# FlasherPanel.net
KiCad netlist of a schematic drawn in EasyEDA Pro
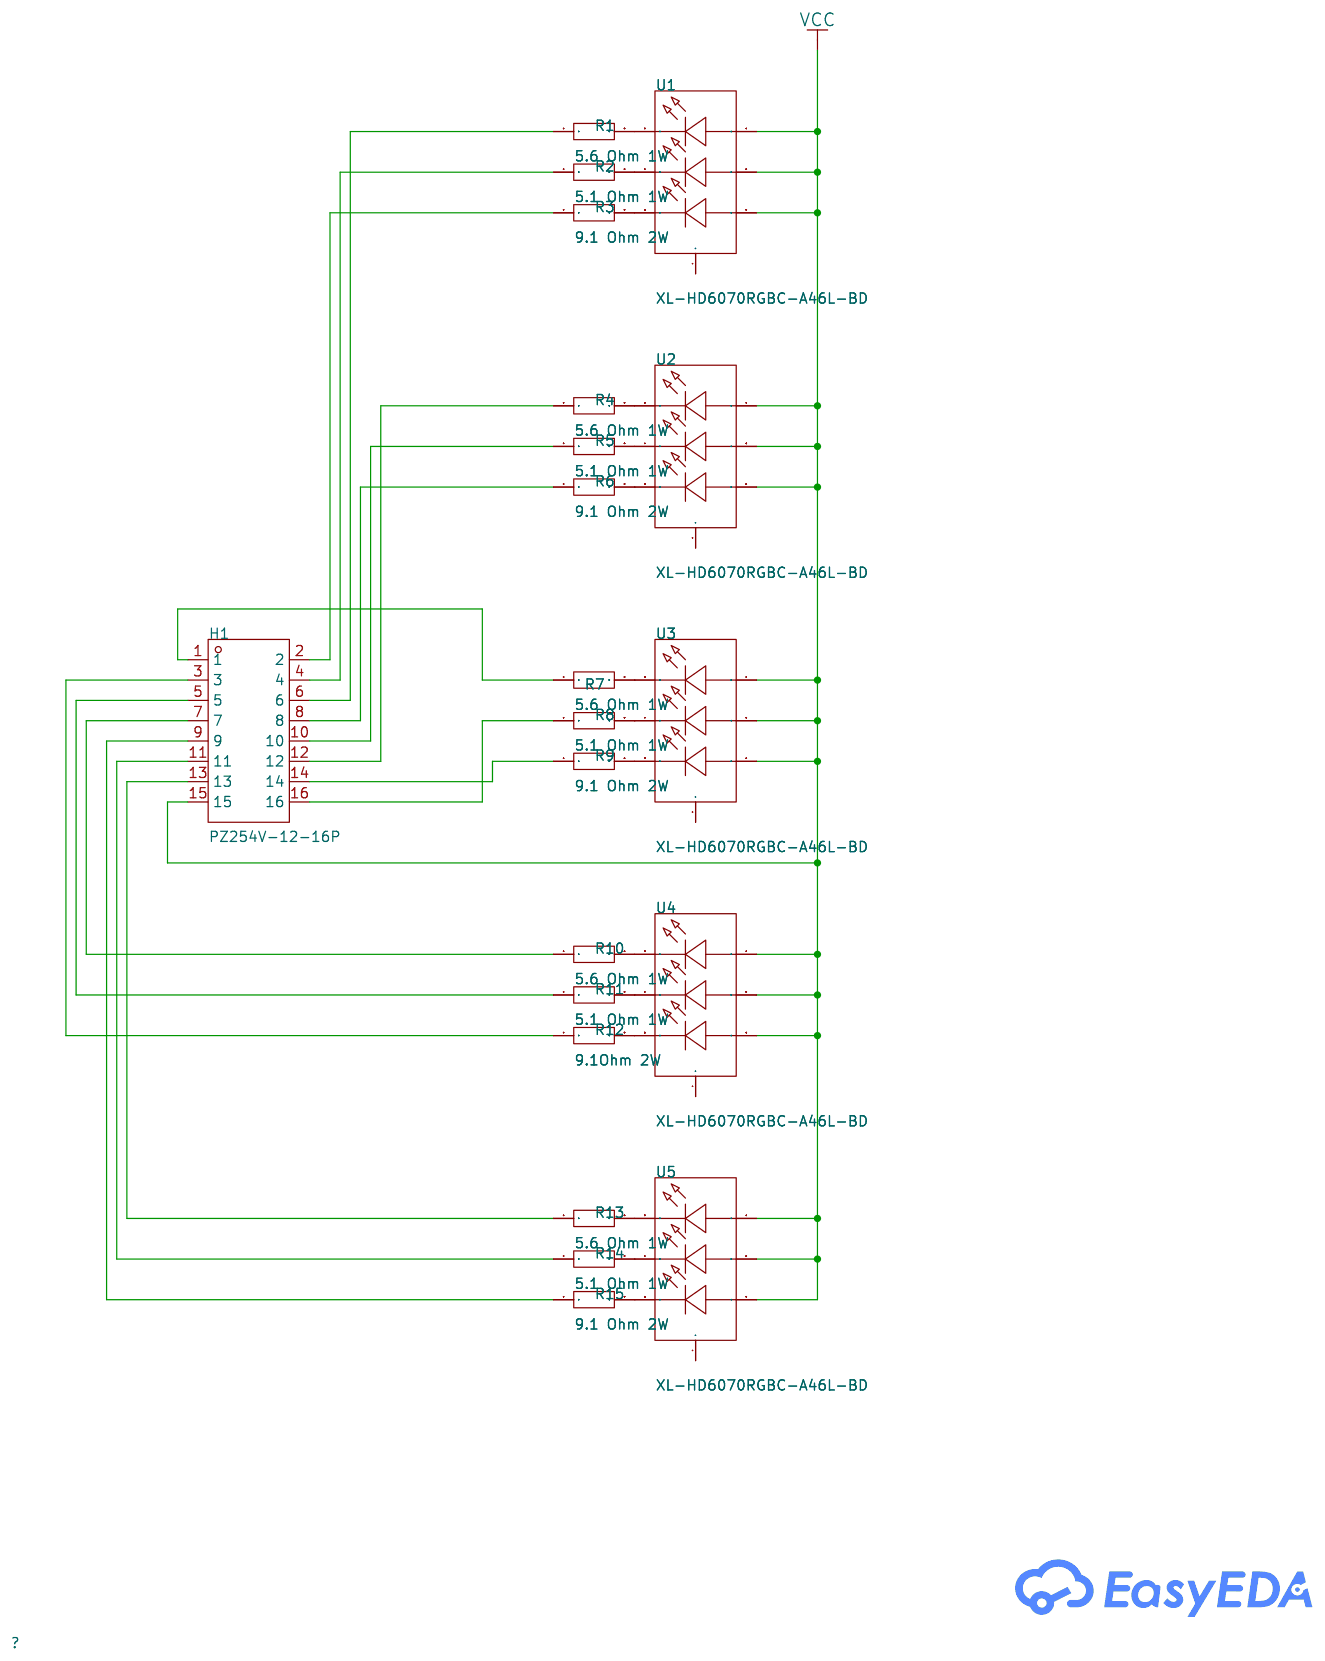
[diagram p0: schematic sheet]

(export (version "E")
  (design (tool "Eeschema 10.0.6"))
  (components
    (comp (ref "H1")
      (value "PZ254V-12-16P")
      (footprint "easyedapro:HDR-TH_16P-P2.54-V-M-R2-C8-S2.54")
      (fields (field (name "Manufacturer") "XFCN(兴飞)"))
      (libsource (lib "easyedapro") (part "PZ254V-12-16P"))
    )
    (comp (ref "R1")
      (value "5.6 Ohm 1W")
      (footprint "easyedapro:R0603")
      (libsource (lib "easyedapro") (part "Res"))
    )
    (comp (ref "R2")
      (value "5.1 Ohm 1W")
      (footprint "easyedapro:R0603")
      (libsource (lib "easyedapro") (part "Res"))
    )
    (comp (ref "R3")
      (value "9.1 Ohm 2W")
      (footprint "easyedapro:R0603")
      (libsource (lib "easyedapro") (part "Res"))
    )
    (comp (ref "R4")
      (value "5.6 Ohm 1W")
      (footprint "easyedapro:R0603")
      (libsource (lib "easyedapro") (part "Res"))
    )
    (comp (ref "R5")
      (value "5.1 Ohm 1W")
      (footprint "easyedapro:R0603")
      (libsource (lib "easyedapro") (part "Res"))
    )
    (comp (ref "R6")
      (value "9.1 Ohm 2W")
      (footprint "easyedapro:R0603")
      (libsource (lib "easyedapro") (part "Res"))
    )
    (comp (ref "R7")
      (value "5.6 Ohm 1W")
      (footprint "easyedapro:R0603")
      (libsource (lib "easyedapro") (part "Res"))
    )
    (comp (ref "R8")
      (value "5.1 Ohm 1W")
      (footprint "easyedapro:R0603")
      (libsource (lib "easyedapro") (part "Res"))
    )
    (comp (ref "R9")
      (value "9.1 Ohm 2W")
      (footprint "easyedapro:R0603")
      (libsource (lib "easyedapro") (part "Res"))
    )
    (comp (ref "R10")
      (value "5.6 Ohm 1W")
      (footprint "easyedapro:R0603")
      (libsource (lib "easyedapro") (part "Res"))
    )
    (comp (ref "R11")
      (value "5.1 Ohm 1W")
      (footprint "easyedapro:R0603")
      (libsource (lib "easyedapro") (part "Res"))
    )
    (comp (ref "R12")
      (value "9.1Ohm 2W")
      (footprint "easyedapro:R0603")
      (libsource (lib "easyedapro") (part "Res"))
    )
    (comp (ref "R13")
      (value "5.6 Ohm 1W")
      (footprint "easyedapro:R0603")
      (libsource (lib "easyedapro") (part "Res"))
    )
    (comp (ref "R14")
      (value "5.1 Ohm 1W")
      (footprint "easyedapro:R0603")
      (libsource (lib "easyedapro") (part "Res"))
    )
    (comp (ref "R15")
      (value "9.1 Ohm 2W")
      (footprint "easyedapro:R0603")
      (libsource (lib "easyedapro") (part "Res"))
    )
    (comp (ref "U1")
      (value "XL-HD6070RGBC-A46L-BD")
      (footprint "easyedapro:LED-SMD_6P-BD8.0-LS14.5")
      (fields (field (name "Manufacturer") "XINGLIGHT(成兴光)"))
      (libsource (lib "easyedapro") (part "XL-HD6070RGBC-A46L-BD"))
    )
    (comp (ref "U2")
      (value "XL-HD6070RGBC-A46L-BD")
      (footprint "easyedapro:LED-SMD_6P-BD8.0-LS14.5")
      (fields (field (name "Manufacturer") "XINGLIGHT(成兴光)"))
      (libsource (lib "easyedapro") (part "XL-HD6070RGBC-A46L-BD"))
    )
    (comp (ref "U3")
      (value "XL-HD6070RGBC-A46L-BD")
      (footprint "easyedapro:LED-SMD_6P-BD8.0-LS14.5")
      (fields (field (name "Manufacturer") "XINGLIGHT(成兴光)"))
      (libsource (lib "easyedapro") (part "XL-HD6070RGBC-A46L-BD"))
    )
    (comp (ref "U4")
      (value "XL-HD6070RGBC-A46L-BD")
      (footprint "easyedapro:LED-SMD_6P-BD8.0-LS14.5")
      (fields (field (name "Manufacturer") "XINGLIGHT(成兴光)"))
      (libsource (lib "easyedapro") (part "XL-HD6070RGBC-A46L-BD"))
    )
    (comp (ref "U5")
      (value "XL-HD6070RGBC-A46L-BD")
      (footprint "easyedapro:LED-SMD_6P-BD8.0-LS14.5")
      (fields (field (name "Manufacturer") "XINGLIGHT(成兴光)"))
      (libsource (lib "easyedapro") (part "XL-HD6070RGBC-A46L-BD"))
    )
  )
  (nets
    (net (code "1") (name "Net-(H1-Pad1)") (class "Default")
      (node (ref "H1") (pin "1") (pinfunction "1_1") (pintype "unspecified"))
      (node (ref "R7") (pin "1") (pinfunction "1_1") (pintype "input"))
    )
    (net (code "2") (name "Net-(H1-Pad2)") (class "Default")
      (node (ref "H1") (pin "2") (pinfunction "2_2") (pintype "unspecified"))
      (node (ref "R3") (pin "1") (pinfunction "1_1") (pintype "input"))
    )
    (net (code "3") (name "Net-(H1-Pad3)") (class "Default")
      (node (ref "H1") (pin "3") (pinfunction "3_3") (pintype "unspecified"))
      (node (ref "R12") (pin "1") (pinfunction "1_1") (pintype "input"))
    )
    (net (code "4") (name "Net-(H1-Pad4)") (class "Default")
      (node (ref "H1") (pin "4") (pinfunction "4_4") (pintype "unspecified"))
      (node (ref "R2") (pin "1") (pinfunction "1_1") (pintype "input"))
    )
    (net (code "5") (name "Net-(H1-Pad5)") (class "Default")
      (node (ref "H1") (pin "5") (pinfunction "5_5") (pintype "unspecified"))
      (node (ref "R11") (pin "1") (pinfunction "1_1") (pintype "input"))
    )
    (net (code "6") (name "Net-(H1-Pad6)") (class "Default")
      (node (ref "H1") (pin "6") (pinfunction "6_6") (pintype "unspecified"))
      (node (ref "R1") (pin "1") (pinfunction "1_1") (pintype "input"))
    )
    (net (code "7") (name "Net-(H1-Pad7)") (class "Default")
      (node (ref "H1") (pin "7") (pinfunction "7_7") (pintype "unspecified"))
      (node (ref "R10") (pin "1") (pinfunction "1_1") (pintype "input"))
    )
    (net (code "8") (name "Net-(H1-Pad8)") (class "Default")
      (node (ref "H1") (pin "8") (pinfunction "8_8") (pintype "unspecified"))
      (node (ref "R6") (pin "1") (pinfunction "1_1") (pintype "input"))
    )
    (net (code "9") (name "Net-(H1-Pad9)") (class "Default")
      (node (ref "H1") (pin "9") (pinfunction "9_9") (pintype "unspecified"))
      (node (ref "R15") (pin "1") (pinfunction "1_1") (pintype "input"))
    )
    (net (code "10") (name "Net-(H1-Pad10)") (class "Default")
      (node (ref "H1") (pin "10") (pinfunction "10_10") (pintype "unspecified"))
      (node (ref "R5") (pin "1") (pinfunction "1_1") (pintype "input"))
    )
    (net (code "11") (name "Net-(H1-Pad11)") (class "Default")
      (node (ref "H1") (pin "11") (pinfunction "11_11") (pintype "unspecified"))
      (node (ref "R14") (pin "1") (pinfunction "1_1") (pintype "input"))
    )
    (net (code "12") (name "Net-(H1-Pad12)") (class "Default")
      (node (ref "H1") (pin "12") (pinfunction "12_12") (pintype "unspecified"))
      (node (ref "R4") (pin "1") (pinfunction "1_1") (pintype "input"))
    )
    (net (code "13") (name "Net-(H1-Pad13)") (class "Default")
      (node (ref "H1") (pin "13") (pinfunction "13_13") (pintype "unspecified"))
      (node (ref "R13") (pin "1") (pinfunction "1_1") (pintype "input"))
    )
    (net (code "14") (name "Net-(H1-Pad14)") (class "Default")
      (node (ref "H1") (pin "14") (pinfunction "14_14") (pintype "unspecified"))
      (node (ref "R9") (pin "1") (pinfunction "1_1") (pintype "input"))
    )
    (net (code "15") (name "Net-(H1-Pad16)") (class "Default")
      (node (ref "H1") (pin "16") (pinfunction "16_16") (pintype "unspecified"))
      (node (ref "R8") (pin "1") (pinfunction "1_1") (pintype "input"))
    )
    (net (code "16") (name "Net-(R1-Pad2)") (class "Default")
      (node (ref "R1") (pin "2") (pinfunction "2_2") (pintype "input"))
      (node (ref "U1") (pin "2") (pinfunction "K_2") (pintype "unspecified"))
    )
    (net (code "17") (name "Net-(R2-Pad2)") (class "Default")
      (node (ref "R2") (pin "2") (pinfunction "2_2") (pintype "input"))
      (node (ref "U1") (pin "4") (pinfunction "K_4") (pintype "unspecified"))
    )
    (net (code "18") (name "Net-(R3-Pad2)") (class "Default")
      (node (ref "R3") (pin "2") (pinfunction "2_2") (pintype "input"))
      (node (ref "U1") (pin "6") (pinfunction "K_6") (pintype "unspecified"))
    )
    (net (code "19") (name "Net-(R4-Pad2)") (class "Default")
      (node (ref "R4") (pin "2") (pinfunction "2_2") (pintype "input"))
      (node (ref "U2") (pin "2") (pinfunction "K_2") (pintype "unspecified"))
    )
    (net (code "20") (name "Net-(R5-Pad2)") (class "Default")
      (node (ref "R5") (pin "2") (pinfunction "2_2") (pintype "input"))
      (node (ref "U2") (pin "4") (pinfunction "K_4") (pintype "unspecified"))
    )
    (net (code "21") (name "Net-(R6-Pad2)") (class "Default")
      (node (ref "R6") (pin "2") (pinfunction "2_2") (pintype "input"))
      (node (ref "U2") (pin "6") (pinfunction "K_6") (pintype "unspecified"))
    )
    (net (code "22") (name "Net-(R7-Pad2)") (class "Default")
      (node (ref "R7") (pin "2") (pinfunction "2_2") (pintype "input"))
      (node (ref "U3") (pin "2") (pinfunction "K_2") (pintype "unspecified"))
    )
    (net (code "23") (name "Net-(R8-Pad2)") (class "Default")
      (node (ref "R8") (pin "2") (pinfunction "2_2") (pintype "input"))
      (node (ref "U3") (pin "4") (pinfunction "K_4") (pintype "unspecified"))
    )
    (net (code "24") (name "Net-(R9-Pad2)") (class "Default")
      (node (ref "R9") (pin "2") (pinfunction "2_2") (pintype "input"))
      (node (ref "U3") (pin "6") (pinfunction "K_6") (pintype "unspecified"))
    )
    (net (code "25") (name "Net-(R10-Pad2)") (class "Default")
      (node (ref "R10") (pin "2") (pinfunction "2_2") (pintype "input"))
      (node (ref "U4") (pin "2") (pinfunction "K_2") (pintype "unspecified"))
    )
    (net (code "26") (name "Net-(R11-Pad2)") (class "Default")
      (node (ref "R11") (pin "2") (pinfunction "2_2") (pintype "input"))
      (node (ref "U4") (pin "4") (pinfunction "K_4") (pintype "unspecified"))
    )
    (net (code "27") (name "Net-(R12-Pad2)") (class "Default")
      (node (ref "R12") (pin "2") (pinfunction "2_2") (pintype "input"))
      (node (ref "U4") (pin "6") (pinfunction "K_6") (pintype "unspecified"))
    )
    (net (code "28") (name "Net-(R13-Pad2)") (class "Default")
      (node (ref "R13") (pin "2") (pinfunction "2_2") (pintype "input"))
      (node (ref "U5") (pin "2") (pinfunction "K_2") (pintype "unspecified"))
    )
    (net (code "29") (name "Net-(R14-Pad2)") (class "Default")
      (node (ref "R14") (pin "2") (pinfunction "2_2") (pintype "input"))
      (node (ref "U5") (pin "4") (pinfunction "K_4") (pintype "unspecified"))
    )
    (net (code "30") (name "Net-(R15-Pad2)") (class "Default")
      (node (ref "R15") (pin "2") (pinfunction "2_2") (pintype "input"))
      (node (ref "U5") (pin "6") (pinfunction "K_6") (pintype "unspecified"))
    )
    (net (code "31") (name "VCC") (class "Default")
      (node (ref "H1") (pin "15") (pinfunction "15_15") (pintype "unspecified"))
      (node (ref "U1") (pin "1") (pinfunction "A_1") (pintype "unspecified"))
      (node (ref "U1") (pin "3") (pinfunction "A_3") (pintype "unspecified"))
      (node (ref "U1") (pin "5") (pinfunction "A_5") (pintype "unspecified"))
      (node (ref "U2") (pin "1") (pinfunction "A_1") (pintype "unspecified"))
      (node (ref "U2") (pin "3") (pinfunction "A_3") (pintype "unspecified"))
      (node (ref "U2") (pin "5") (pinfunction "A_5") (pintype "unspecified"))
      (node (ref "U3") (pin "1") (pinfunction "A_1") (pintype "unspecified"))
      (node (ref "U3") (pin "3") (pinfunction "A_3") (pintype "unspecified"))
      (node (ref "U3") (pin "5") (pinfunction "A_5") (pintype "unspecified"))
      (node (ref "U4") (pin "1") (pinfunction "A_1") (pintype "unspecified"))
      (node (ref "U4") (pin "3") (pinfunction "A_3") (pintype "unspecified"))
      (node (ref "U4") (pin "5") (pinfunction "A_5") (pintype "unspecified"))
      (node (ref "U5") (pin "1") (pinfunction "A_1") (pintype "unspecified"))
      (node (ref "U5") (pin "3") (pinfunction "A_3") (pintype "unspecified"))
      (node (ref "U5") (pin "5") (pinfunction "A_5") (pintype "unspecified"))
    )
    (net (code "32") (name "unconnected-(U1-Pad7)") (class "Default")
      (node (ref "U1") (pin "7") (pinfunction "7_7") (pintype "unspecified"))
    )
    (net (code "33") (name "unconnected-(U2-Pad7)") (class "Default")
      (node (ref "U2") (pin "7") (pinfunction "7_7") (pintype "unspecified"))
    )
    (net (code "34") (name "unconnected-(U3-Pad7)") (class "Default")
      (node (ref "U3") (pin "7") (pinfunction "7_7") (pintype "unspecified"))
    )
    (net (code "35") (name "unconnected-(U4-Pad7)") (class "Default")
      (node (ref "U4") (pin "7") (pinfunction "7_7") (pintype "unspecified"))
    )
    (net (code "36") (name "unconnected-(U5-Pad7)") (class "Default")
      (node (ref "U5") (pin "7") (pinfunction "7_7") (pintype "unspecified"))
    )
  )
)
